# IRS2092_CONTROLLER.net
KiCad netlist of a schematic drawn in Altium Designer
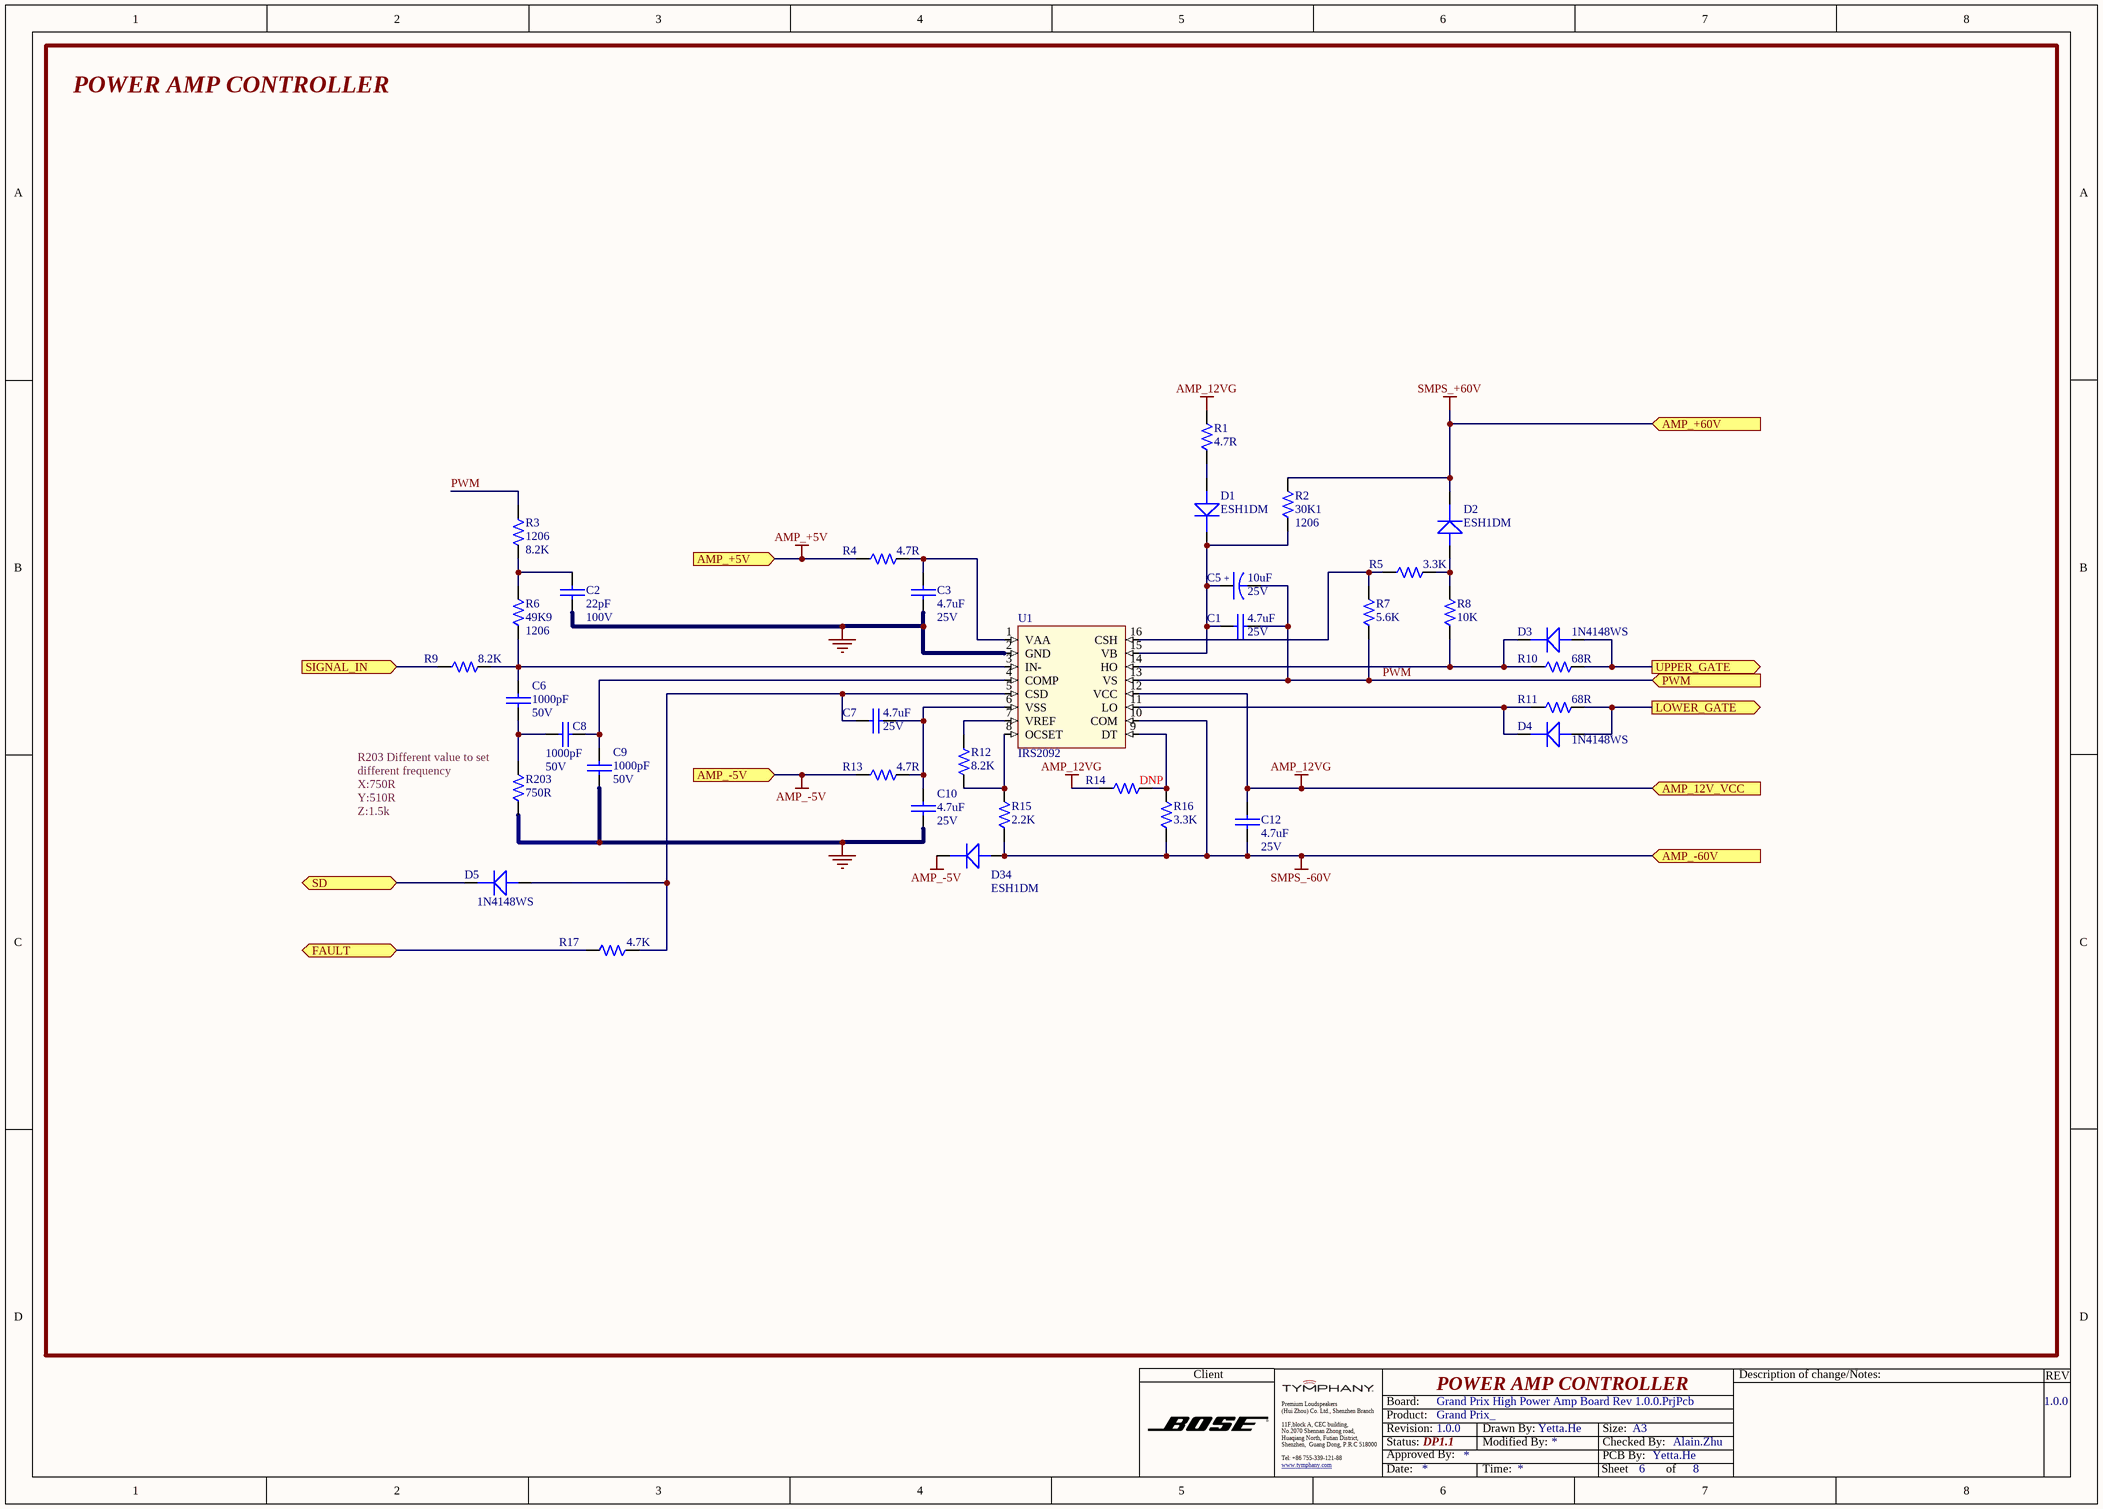
[diagram p0: IRS2092 CONTROLLER.SchDoc]

(export (version "E")
  (design (tool "Eeschema 10.0.6"))
  (components
    (comp (ref "C1")
      (value "4.7uF")
      (footprint "CAPC0603-RW")
      (description "CAP X7R 4.7UF 25V +-10% 0603 WALSIN L")
      (fields
        (field (name "MFG") "WALSIN")
        (field (name "TOLERANCE") "10%")
        (field (name "VOLTAGE") "25V")
        (field (name "CREATE_NAME") "Nathan")
      )
      (libsource (lib "P-Capacitors") (part "CAP0603 4.7uF 25V 10%_X7R_WALSIN"))
    )
    (comp (ref "C2")
      (value "22pF")
      (footprint "CAPC0805-RW")
      (description "CAP NPO 22PF 100V +-5% 0805 WALSIN L")
      (fields
        (field (name "MFG") "WALSIN")
        (field (name "TOLERANCE") "5%")
        (field (name "VOLTAGE") "100V")
        (field (name "CREATE_NAME") "Nathan")
      )
      (libsource (lib "P-Capacitors") (part "CAPC0805 22pF 100V 5%_NPO_WALSIN"))
    )
    (comp (ref "C3")
      (value "4.7uF")
      (footprint "CAPC0603-RW")
      (description "CAP X7R 4.7UF 25V +-10% 0603 WALSIN L")
      (fields
        (field (name "MFG") "WALSIN")
        (field (name "TOLERANCE") "10%")
        (field (name "VOLTAGE") "25V")
        (field (name "CREATE_NAME") "Nathan")
      )
      (libsource (lib "P-Capacitors") (part "CAP0603 4.7uF 25V 10%_X7R_WALSIN"))
    )
    (comp (ref "C5")
      (value "10uF")
      (footprint "CASE - B")
      (description "E 10UF 25V +-20% 4.3X5 VEJ100M1E")
      (fields
        (field (name "MFG") "LELON")
        (field (name "MFG PART") "VEJ100M1ETR-0405")
        (field (name "VOLTAGE") "25V")
        (field (name "CREATE_NAME") "Cherry")
      )
      (libsource (lib "Temporary") (part "CAP E 10uF 25V 20% SMD_VEJ100M1ETR-0405"))
    )
    (comp (ref "C6")
      (value "1000pF")
      (footprint "CAPC0603-RW")
      (description "CHIP CAP 1000pF 50V 5% 0603 TYPE NPO")
      (fields
        (field (name "TOLERANCE") "5%")
        (field (name "VOLTAGE") "50V")
        (field (name "Comment") "PXL410370-1020")
      )
      (libsource (lib "P-Capacitors") (part "CAP0603 1000pF 50V 5% - PXL410370-1020"))
    )
    (comp (ref "C7")
      (value "4.7uF")
      (footprint "CAPC0603-RW")
      (description "CAP X7R 4.7UF 25V +-10% 0603 WALSIN L")
      (fields
        (field (name "MFG") "WALSIN")
        (field (name "TOLERANCE") "10%")
        (field (name "VOLTAGE") "25V")
        (field (name "CREATE_NAME") "Nathan")
      )
      (libsource (lib "P-Capacitors") (part "CAP0603 4.7uF 25V 10%_X7R_WALSIN"))
    )
    (comp (ref "C8")
      (value "1000pF")
      (footprint "CAPC0603-RW")
      (description "CHIP CAP 1000pF 50V 5% 0603 TYPE NPO")
      (fields
        (field (name "TOLERANCE") "5%")
        (field (name "VOLTAGE") "50V")
        (field (name "Comment") "PXL410370-1020")
      )
      (libsource (lib "P-Capacitors") (part "CAP0603 1000pF 50V 5% - PXL410370-1020"))
    )
    (comp (ref "C9")
      (value "1000pF")
      (footprint "CAPC0603-RW")
      (description "CHIP CAP 1000pF 50V 5% 0603 TYPE NPO")
      (fields
        (field (name "TOLERANCE") "5%")
        (field (name "VOLTAGE") "50V")
        (field (name "Comment") "PXL410370-1020")
      )
      (libsource (lib "P-Capacitors") (part "CAP0603 1000pF 50V 5% - PXL410370-1020"))
    )
    (comp (ref "C10")
      (value "4.7uF")
      (footprint "CAPC0603-RW")
      (description "CAP X7R 4.7UF 25V +-10% 0603 WALSIN L")
      (fields
        (field (name "MFG") "WALSIN")
        (field (name "TOLERANCE") "10%")
        (field (name "VOLTAGE") "25V")
        (field (name "CREATE_NAME") "Nathan")
      )
      (libsource (lib "P-Capacitors") (part "CAP0603 4.7uF 25V 10%_X7R_WALSIN"))
    )
    (comp (ref "C12")
      (value "4.7uF")
      (footprint "CAPC0603-RW")
      (description "CAP X7R 4.7UF 25V +-10% 0603 WALSIN L")
      (fields
        (field (name "MFG") "WALSIN")
        (field (name "TOLERANCE") "10%")
        (field (name "VOLTAGE") "25V")
        (field (name "CREATE_NAME") "Nathan")
      )
      (libsource (lib "P-Capacitors") (part "CAP0603 4.7uF 25V 10%_X7R_WALSIN"))
    )
    (comp (ref "D1")
      (value "T571002680204")
      (footprint "Micro SMA")
      (description "DIODE 200V 1.0A ESH1DM TSC G")
      (fields
        (field (name "MFG") "TSC")
        (field (name "VOLTAGE") "200V")
        (field (name "MFG PART") "ESH1DM")
        (field (name "CREATE_NAME") "Tom")
      )
      (libsource (lib "R-Semiconductors") (part "ESH1DM"))
    )
    (comp (ref "D2")
      (value "T571002680204")
      (footprint "Micro SMA")
      (description "DIODE 200V 1.0A ESH1DM TSC G")
      (fields
        (field (name "MFG") "TSC")
        (field (name "VOLTAGE") "200V")
        (field (name "MFG PART") "ESH1DM")
        (field (name "CREATE_NAME") "Tom")
      )
      (libsource (lib "R-Semiconductors") (part "ESH1DM"))
    )
    (comp (ref "D3")
      (value "RCD114148-0020")
      (footprint "SOD-323")
      (description "DIODE SW 1N4148 VF=0.7V SOD-323")
      (fields
        (field (name "MFG") "TW SEMICONDUCTOR")
        (field (name "VOLTAGE") "100V")
        (field (name "MFG PART") "1N4148WS")
      )
      (libsource (lib "R-Semiconductors") (part "1N4148WS"))
    )
    (comp (ref "D4")
      (value "RCD114148-0020")
      (footprint "SOD-323")
      (description "DIODE SW 1N4148 VF=0.7V SOD-323")
      (fields
        (field (name "MFG") "TW SEMICONDUCTOR")
        (field (name "VOLTAGE") "100V")
        (field (name "MFG PART") "1N4148WS")
      )
      (libsource (lib "R-Semiconductors") (part "1N4148WS"))
    )
    (comp (ref "D5")
      (value "RCD114148-0020")
      (footprint "SOD-323")
      (description "DIODE SW 1N4148 VF=0.7V SOD-323")
      (fields
        (field (name "MFG") "TW SEMICONDUCTOR")
        (field (name "VOLTAGE") "100V")
        (field (name "MFG PART") "1N4148WS")
      )
      (libsource (lib "R-Semiconductors") (part "1N4148WS"))
    )
    (comp (ref "D34")
      (value "T571002680204")
      (footprint "Micro SMA")
      (description "DIODE 200V 1.0A ESH1DM TSC G")
      (fields
        (field (name "MFG") "TSC")
        (field (name "VOLTAGE") "200V")
        (field (name "MFG PART") "ESH1DM")
        (field (name "CREATE_NAME") "Tom")
      )
      (libsource (lib "R-Semiconductors") (part "ESH1DM"))
    )
    (comp (ref "R1")
      (value "4.7R")
      (footprint "0805-RW")
      (description "GP CHIP RES 4.7 OHM 1/8W 1% 0805")
      (fields (field (name "POWER") "1/8W") (field (name "Comment") "QCF081020-4708"))
      (libsource (lib "Q-Resistors") (part "RES0805 1/8W 1% 4.7 OHM"))
    )
    (comp (ref "R2")
      (value "30K1")
      (footprint "1206-RW")
      (description "CHIP 30.1K OHM 100PPM +-1% 1206 WALS L")
      (fields
        (field (name "POWER") "1/4W")
        (field (name "MFG") "WALSIN (華新)")
        (field (name "PACKAGE") "1206")
        (field (name "CREATE_NAME") "Nathan")
      )
      (libsource (lib "Q-Resistors") (part "RES1206 1/4W 1% 30.1K OHM_WALSIN"))
    )
    (comp (ref "R3")
      (value "8.2K")
      (footprint "1206-RW")
      (description "CHIP 8.2K OHM 100PPM +-1% 1206 WALS L")
      (fields
        (field (name "MFG PART") "WR12X8201FTL")
        (field (name "MFG") "WALSIN")
        (field (name "PACKAGE") "1206")
        (field (name "CREATE_NAME") "Tom")
      )
      (libsource (lib "Q-Resistors") (part "RES1206 1/4W 1% 8.2K OHM"))
    )
    (comp (ref "R4")
      (value "4.7R")
      (footprint "0603-RW")
      (description "CHIP RES. 4.7 OHM 1/10W 1% 0603")
      (fields (field (name "POWER") "1/10W") (field (name "Comment") "QCF011030-4708"))
      (libsource (lib "Q-Resistors") (part "RES0603 1/10W 1% 4.7 OHM"))
    )
    (comp (ref "R5")
      (value "3.3K")
      (footprint "0603-RW")
      (description "GP CHIP RES. 3.3K OHM 1/10W 1% 0603")
      (fields (field (name "POWER") "1/10W") (field (name "Comment") "QCF011030-3301"))
      (libsource (lib "Q-Resistors") (part "RES0603 1/10W 1% 3.3K OHM"))
    )
    (comp (ref "R6")
      (value "49K9")
      (footprint "1206-RW")
      (description "CHIP 49.9K OHM 100PPM +-1% 1206 WALS L")
      (fields
        (field (name "POWER") "1/4W")
        (field (name "MFG") "WALSIN (華新)")
        (field (name "PACKAGE") "1206")
        (field (name "CREATE_NAME") "Nathan")
      )
      (libsource (lib "Q-Resistors") (part "RES1206 1/4W 1% 49.9K OHM_WALSIN"))
    )
    (comp (ref "R7")
      (value "5.6K")
      (footprint "0603-RW")
      (description "GP CHIP RES. 5.6K OHM 1/10W 1% 0603")
      (fields (field (name "POWER") "1/10W") (field (name "Comment") "QCF011030-5601"))
      (libsource (lib "Q-Resistors") (part "RES0603 1/10W 1% 5.6K OHM"))
    )
    (comp (ref "R8")
      (value "10K")
      (footprint "0603-RW")
      (description "GP CHIP RES. 10K OHM 1/10W 1% 0603")
      (fields (field (name "POWER") "1/10W") (field (name "Comment") "QCF011030-1002"))
      (libsource (lib "Q-Resistors") (part "RES0603 1/10W 1% 10K OHM"))
    )
    (comp (ref "R9")
      (value "8.2K")
      (footprint "0603-RW")
      (description "GP CHIP RES. 8.2K OHM 1/10W 1% 0603")
      (fields (field (name "POWER") "1/10W") (field (name "Comment") "QCF011030-8201"))
      (libsource (lib "Q-Resistors") (part "RES0603 1/10W 1% 8.2K OHM"))
    )
    (comp (ref "R10")
      (value "68R")
      (footprint "0805-RW")
      (description "GP CHIP RES. 68 OHM 1/8W 1% 0805")
      (fields (field (name "POWER") "1/8W") (field (name "MFG") "WALSIN"))
      (libsource (lib "Q-Resistors") (part "RES0805 1/8W 1% 68 OHM"))
    )
    (comp (ref "R11")
      (value "68R")
      (footprint "0805-RW")
      (description "GP CHIP RES. 68 OHM 1/8W 1% 0805")
      (fields (field (name "POWER") "1/8W") (field (name "MFG") "WALSIN"))
      (libsource (lib "Q-Resistors") (part "RES0805 1/8W 1% 68 OHM"))
    )
    (comp (ref "R12")
      (value "8.2K")
      (footprint "0603-RW")
      (description "GP CHIP RES. 8.2K OHM 1/10W 1% 0603")
      (fields (field (name "POWER") "1/10W") (field (name "Comment") "QCF011030-8201"))
      (libsource (lib "Q-Resistors") (part "RES0603 1/10W 1% 8.2K OHM"))
    )
    (comp (ref "R13")
      (value "4.7R")
      (footprint "0603-RW")
      (description "CHIP RES. 4.7 OHM 1/10W 1% 0603")
      (fields (field (name "POWER") "1/10W") (field (name "Comment") "QCF011030-4708"))
      (libsource (lib "Q-Resistors") (part "RES0603 1/10W 1% 4.7 OHM"))
    )
    (comp (ref "R14")
      (value "DNP")
      (footprint "0603-RW")
      (description "NC")
      (fields (field (name "Comment") "RES0603 NC") (field (name "CREATE_NAME") "Tom"))
      (libsource (lib "Temporary") (part "RES0603 NC"))
    )
    (comp (ref "R15")
      (value "2.2K")
      (footprint "0603-RW")
      (description "GP CHIP RES. 2.2K OHM 1/10W 1% 0603")
      (fields (field (name "POWER") "1/10W") (field (name "Comment") "QCF011030-2201"))
      (libsource (lib "Q-Resistors") (part "RES0603 1/10W 1% 2.2K OHM"))
    )
    (comp (ref "R16")
      (value "3.3K")
      (footprint "0603-RW")
      (description "GP CHIP RES. 3.3K OHM 1/10W 1% 0603")
      (fields (field (name "POWER") "1/10W") (field (name "Comment") "QCF011030-3301"))
      (libsource (lib "Q-Resistors") (part "RES0603 1/10W 1% 3.3K OHM"))
    )
    (comp (ref "R17")
      (value "4.7K")
      (footprint "0603-RW")
      (description "GP CHIP RES. 4.7K OHM 1/10W 1% 0603")
      (fields (field (name "POWER") "1/10W") (field (name "Comment") "QCF011030-4701"))
      (libsource (lib "Q-Resistors") (part "RES0603 1/10W 1% 4.7K OHM"))
    )
    (comp (ref "R203")
      (value "750R")
      (footprint "0603-RW")
      (description "GP CHIP RES. 750 OHM 1/10W 1% 0603")
      (fields (field (name "POWER") "1/10W") (field (name "Comment") "QCF011030-7500"))
      (libsource (lib "Q-Resistors") (part "RES0603 1/10W 1% 750 OHM"))
    )
    (comp (ref "U1")
      (value "RCI002092-0001")
      (footprint "SO16")
      (description "IC 16P IRS2092S SOIC16N")
      (fields (field (name "MFG") "IR") (field (name "MFG PART") "IRS2092"))
      (libsource (lib "R-Semiconductors") (part "IRS2092"))
    )
  )
  (nets
    (net (code "1") (name "/FAULT") (class "Default")
      (node (ref "R17") (pin "2") (pinfunction "2_2") (pintype "passive"))
    )
    (net (code "2") (name "/LOWER_GATE") (class "Default")
      (node (ref "D4") (pin "1") (pinfunction "A_1") (pintype "passive"))
      (node (ref "R11") (pin "2") (pinfunction "2_2") (pintype "passive"))
    )
    (net (code "3") (name "/PWM") (class "Default")
      (node (ref "C1") (pin "2") (pinfunction "2_2") (pintype "passive"))
      (node (ref "C5") (pin "2") (pinfunction "2_2") (pintype "passive"))
      (node (ref "R3") (pin "1") (pinfunction "1_1") (pintype "passive"))
      (node (ref "R7") (pin "1") (pinfunction "1_1") (pintype "passive"))
      (node (ref "U1") (pin "13") (pinfunction "VS_13") (pintype "input"))
    )
    (net (code "4") (name "/SD") (class "Default")
      (node (ref "D5") (pin "2") (pinfunction "K_2") (pintype "passive"))
    )
    (net (code "5") (name "/SIGNAL_IN") (class "Default")
      (node (ref "R9") (pin "1") (pinfunction "1_1") (pintype "passive"))
    )
    (net (code "6") (name "/UPPER_GATE") (class "Default")
      (node (ref "D3") (pin "1") (pinfunction "A_1") (pintype "passive"))
      (node (ref "R10") (pin "2") (pinfunction "2_2") (pintype "passive"))
    )
    (net (code "7") (name "AMP_+5V") (class "Default")
      (node (ref "R4") (pin "1") (pinfunction "1_1") (pintype "passive"))
    )
    (net (code "8") (name "AMP_-5V") (class "Default")
      (node (ref "D34") (pin "2") (pinfunction "K_2") (pintype "passive"))
      (node (ref "R13") (pin "1") (pinfunction "1_1") (pintype "passive"))
    )
    (net (code "9") (name "AMP_12VG") (class "Default")
      (node (ref "C12") (pin "1") (pinfunction "1_1") (pintype "passive"))
      (node (ref "R1") (pin "2") (pinfunction "2_2") (pintype "passive"))
      (node (ref "R14") (pin "1") (pinfunction "1_1") (pintype "passive"))
      (node (ref "U1") (pin "12") (pinfunction "VCC_12") (pintype "input"))
    )
    (net (code "10") (name "GND") (class "Default")
      (node (ref "C10") (pin "2") (pinfunction "2_2") (pintype "passive"))
      (node (ref "C2") (pin "2") (pinfunction "2_2") (pintype "passive"))
      (node (ref "C3") (pin "2") (pinfunction "2_2") (pintype "passive"))
      (node (ref "C9") (pin "2") (pinfunction "2_2") (pintype "passive"))
      (node (ref "R203") (pin "1") (pinfunction "1_1") (pintype "passive"))
      (node (ref "U1") (pin "2") (pinfunction "GND_2") (pintype "input"))
    )
    (net (code "11") (name "Net-(C2-Pad1)") (class "Default")
      (node (ref "C2") (pin "1") (pinfunction "1_1") (pintype "passive"))
      (node (ref "R3") (pin "2") (pinfunction "2_2") (pintype "passive"))
      (node (ref "R6") (pin "2") (pinfunction "2_2") (pintype "passive"))
    )
    (net (code "12") (name "Net-(C6-Pad2)") (class "Default")
      (node (ref "C6") (pin "2") (pinfunction "2_2") (pintype "passive"))
      (node (ref "C8") (pin "1") (pinfunction "1_1") (pintype "passive"))
      (node (ref "R203") (pin "2") (pinfunction "2_2") (pintype "passive"))
    )
    (net (code "13") (name "Net-(D1-A)") (class "Default")
      (node (ref "D1") (pin "1") (pinfunction "A_1") (pintype "passive"))
      (node (ref "R1") (pin "1") (pinfunction "1_1") (pintype "passive"))
    )
    (net (code "14") (name "Net-(D1-K)") (class "Default")
      (node (ref "C1") (pin "1") (pinfunction "1_1") (pintype "passive"))
      (node (ref "C5") (pin "1") (pinfunction "1_1") (pintype "passive"))
      (node (ref "D1") (pin "2") (pinfunction "K_2") (pintype "passive"))
      (node (ref "R2") (pin "1") (pinfunction "1_1") (pintype "passive"))
      (node (ref "U1") (pin "15") (pinfunction "VB_15") (pintype "input"))
    )
    (net (code "15") (name "Net-(D2-A)") (class "Default")
      (node (ref "D2") (pin "1") (pinfunction "A_1") (pintype "passive"))
      (node (ref "R5") (pin "2") (pinfunction "2_2") (pintype "passive"))
      (node (ref "R8") (pin "2") (pinfunction "2_2") (pintype "passive"))
    )
    (net (code "16") (name "Net-(D3-K)") (class "Default")
      (node (ref "D3") (pin "2") (pinfunction "K_2") (pintype "passive"))
      (node (ref "R10") (pin "1") (pinfunction "1_1") (pintype "passive"))
      (node (ref "R8") (pin "1") (pinfunction "1_1") (pintype "passive"))
      (node (ref "U1") (pin "14") (pinfunction "HO_14") (pintype "input"))
    )
    (net (code "17") (name "Net-(D4-K)") (class "Default")
      (node (ref "D4") (pin "2") (pinfunction "K_2") (pintype "passive"))
      (node (ref "R11") (pin "1") (pinfunction "1_1") (pintype "passive"))
      (node (ref "U1") (pin "11") (pinfunction "LO_11") (pintype "input"))
    )
    (net (code "18") (name "Net-(D5-A)") (class "Default")
      (node (ref "C7") (pin "1") (pinfunction "1_1") (pintype "passive"))
      (node (ref "D5") (pin "1") (pinfunction "A_1") (pintype "passive"))
      (node (ref "R17") (pin "1") (pinfunction "1_1") (pintype "passive"))
      (node (ref "U1") (pin "5") (pinfunction "CSD_5") (pintype "input"))
    )
    (net (code "19") (name "Net-(U1-COMP)") (class "Default")
      (node (ref "C8") (pin "2") (pinfunction "2_2") (pintype "passive"))
      (node (ref "C9") (pin "1") (pinfunction "1_1") (pintype "passive"))
      (node (ref "U1") (pin "4") (pinfunction "COMP_4") (pintype "input"))
    )
    (net (code "20") (name "Net-(U1-CSH)") (class "Default")
      (node (ref "R5") (pin "1") (pinfunction "1_1") (pintype "passive"))
      (node (ref "R7") (pin "2") (pinfunction "2_2") (pintype "passive"))
      (node (ref "U1") (pin "16") (pinfunction "CSH_16") (pintype "input"))
    )
    (net (code "21") (name "Net-(U1-DT)") (class "Default")
      (node (ref "R14") (pin "2") (pinfunction "2_2") (pintype "passive"))
      (node (ref "R16") (pin "2") (pinfunction "2_2") (pintype "passive"))
      (node (ref "U1") (pin "9") (pinfunction "DT_9") (pintype "input"))
    )
    (net (code "22") (name "Net-(U1-IN-)") (class "Default")
      (node (ref "C6") (pin "1") (pinfunction "1_1") (pintype "passive"))
      (node (ref "R6") (pin "1") (pinfunction "1_1") (pintype "passive"))
      (node (ref "R9") (pin "2") (pinfunction "2_2") (pintype "passive"))
      (node (ref "U1") (pin "3") (pinfunction "IN-_3") (pintype "input"))
    )
    (net (code "23") (name "Net-(U1-OCSET)") (class "Default")
      (node (ref "R12") (pin "2") (pinfunction "2_2") (pintype "passive"))
      (node (ref "R15") (pin "2") (pinfunction "2_2") (pintype "passive"))
      (node (ref "U1") (pin "8") (pinfunction "OCSET_8") (pintype "input"))
    )
    (net (code "24") (name "Net-(U1-VAA)") (class "Default")
      (node (ref "C3") (pin "1") (pinfunction "1_1") (pintype "passive"))
      (node (ref "R4") (pin "2") (pinfunction "2_2") (pintype "passive"))
      (node (ref "U1") (pin "1") (pinfunction "VAA_1") (pintype "input"))
    )
    (net (code "25") (name "Net-(U1-VREF)") (class "Default")
      (node (ref "R12") (pin "1") (pinfunction "1_1") (pintype "passive"))
      (node (ref "U1") (pin "7") (pinfunction "VREF_7") (pintype "input"))
    )
    (net (code "26") (name "Net-(U1-VSS)") (class "Default")
      (node (ref "C10") (pin "1") (pinfunction "1_1") (pintype "passive"))
      (node (ref "C7") (pin "2") (pinfunction "2_2") (pintype "passive"))
      (node (ref "R13") (pin "2") (pinfunction "2_2") (pintype "passive"))
      (node (ref "U1") (pin "6") (pinfunction "VSS_6") (pintype "input"))
    )
    (net (code "27") (name "SMPS_+60V") (class "Default")
      (node (ref "D2") (pin "2") (pinfunction "K_2") (pintype "passive"))
      (node (ref "R2") (pin "2") (pinfunction "2_2") (pintype "passive"))
    )
    (net (code "28") (name "SMPS_-60V") (class "Default")
      (node (ref "C12") (pin "2") (pinfunction "2_2") (pintype "passive"))
      (node (ref "D34") (pin "1") (pinfunction "A_1") (pintype "passive"))
      (node (ref "R15") (pin "1") (pinfunction "1_1") (pintype "passive"))
      (node (ref "R16") (pin "1") (pinfunction "1_1") (pintype "passive"))
      (node (ref "U1") (pin "10") (pinfunction "COM_10") (pintype "input"))
    )
  )
)
